# design.net
KiCad netlist of a schematic drawn in EasyEDA Pro
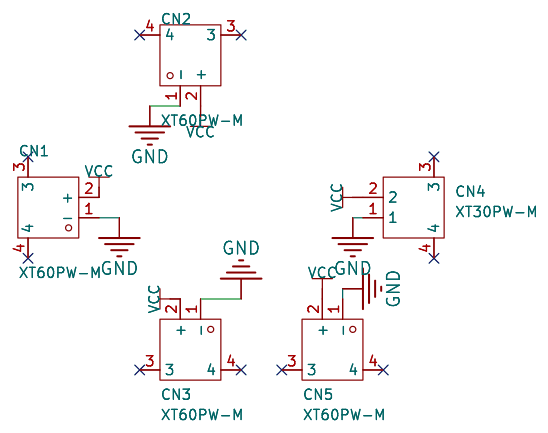
[diagram p0: schematic sheet]

(export (version "E")
  (design (tool "Eeschema 10.0.6"))
  (components
    (comp (ref "CN1")
      (value "XT60PW-M")
      (footprint "easyedapro:CONN-TH_XT60PW-M")
      (description "类别:-;类型1:-;")
      (fields (field (name "Manufacturer") "AMASS(艾迈斯)"))
      (libsource (lib "easyedapro") (part "XT60PW-M"))
    )
    (comp (ref "CN2")
      (value "XT60PW-M")
      (footprint "easyedapro:CONN-TH_XT60PW-M")
      (description "类别:-;类型1:-;")
      (fields (field (name "Manufacturer") "AMASS(艾迈斯)"))
      (libsource (lib "easyedapro") (part "XT60PW-M"))
    )
    (comp (ref "CN3")
      (value "XT60PW-M")
      (footprint "easyedapro:CONN-TH_XT60PW-M")
      (description "类别:-;类型1:-;")
      (fields (field (name "Manufacturer") "AMASS(艾迈斯)"))
      (libsource (lib "easyedapro") (part "XT60PW-M"))
    )
    (comp (ref "CN4")
      (value "XT30PW-M")
      (footprint "easyedapro:CONN-TH_XT30PW-M")
      (description "类别:-;类型1:-;")
      (fields (field (name "Manufacturer") "AMASS(艾迈斯)"))
      (libsource (lib "easyedapro") (part "XT30PW-M"))
    )
    (comp (ref "CN5")
      (value "XT60PW-M")
      (footprint "easyedapro:CONN-TH_XT60PW-M")
      (description "类别:-;类型1:-;")
      (fields (field (name "Manufacturer") "AMASS(艾迈斯)"))
      (libsource (lib "easyedapro") (part "XT60PW-M"))
    )
  )
  (nets
    (net (code "1") (name "GND") (class "Default")
      (node (ref "CN1") (pin "1") (pinfunction "-_1") (pintype "unspecified"))
      (node (ref "CN2") (pin "1") (pinfunction "-_1") (pintype "unspecified"))
      (node (ref "CN3") (pin "1") (pinfunction "-_1") (pintype "unspecified"))
      (node (ref "CN4") (pin "1") (pinfunction "1_1") (pintype "unspecified"))
      (node (ref "CN5") (pin "1") (pinfunction "-_1") (pintype "unspecified"))
    )
    (net (code "2") (name "VCC") (class "Default")
      (node (ref "CN1") (pin "2") (pinfunction "+_2") (pintype "unspecified"))
      (node (ref "CN2") (pin "2") (pinfunction "+_2") (pintype "unspecified"))
      (node (ref "CN3") (pin "2") (pinfunction "+_2") (pintype "unspecified"))
      (node (ref "CN4") (pin "2") (pinfunction "2_2") (pintype "unspecified"))
      (node (ref "CN5") (pin "2") (pinfunction "+_2") (pintype "unspecified"))
    )
    (net (code "3") (name "unconnected-(CN1-Pad3)") (class "Default")
      (node (ref "CN1") (pin "3") (pinfunction "3_3") (pintype "unspecified+no_connect"))
    )
    (net (code "4") (name "unconnected-(CN1-Pad4)") (class "Default")
      (node (ref "CN1") (pin "4") (pinfunction "4_4") (pintype "unspecified+no_connect"))
    )
    (net (code "5") (name "unconnected-(CN2-Pad3)") (class "Default")
      (node (ref "CN2") (pin "3") (pinfunction "3_3") (pintype "unspecified+no_connect"))
    )
    (net (code "6") (name "unconnected-(CN2-Pad4)") (class "Default")
      (node (ref "CN2") (pin "4") (pinfunction "4_4") (pintype "unspecified+no_connect"))
    )
    (net (code "7") (name "unconnected-(CN3-Pad3)") (class "Default")
      (node (ref "CN3") (pin "3") (pinfunction "3_3") (pintype "unspecified+no_connect"))
    )
    (net (code "8") (name "unconnected-(CN3-Pad4)") (class "Default")
      (node (ref "CN3") (pin "4") (pinfunction "4_4") (pintype "unspecified+no_connect"))
    )
    (net (code "9") (name "unconnected-(CN4-Pad3)") (class "Default")
      (node (ref "CN4") (pin "3") (pinfunction "3_3") (pintype "unspecified+no_connect"))
    )
    (net (code "10") (name "unconnected-(CN4-Pad4)") (class "Default")
      (node (ref "CN4") (pin "4") (pinfunction "4_4") (pintype "unspecified+no_connect"))
    )
    (net (code "11") (name "unconnected-(CN5-Pad3)") (class "Default")
      (node (ref "CN5") (pin "3") (pinfunction "3_3") (pintype "unspecified+no_connect"))
    )
    (net (code "12") (name "unconnected-(CN5-Pad4)") (class "Default")
      (node (ref "CN5") (pin "4") (pinfunction "4_4") (pintype "unspecified+no_connect"))
    )
  )
)
